# H1BR6.net
KiCad netlist of a schematic drawn in EAGLE
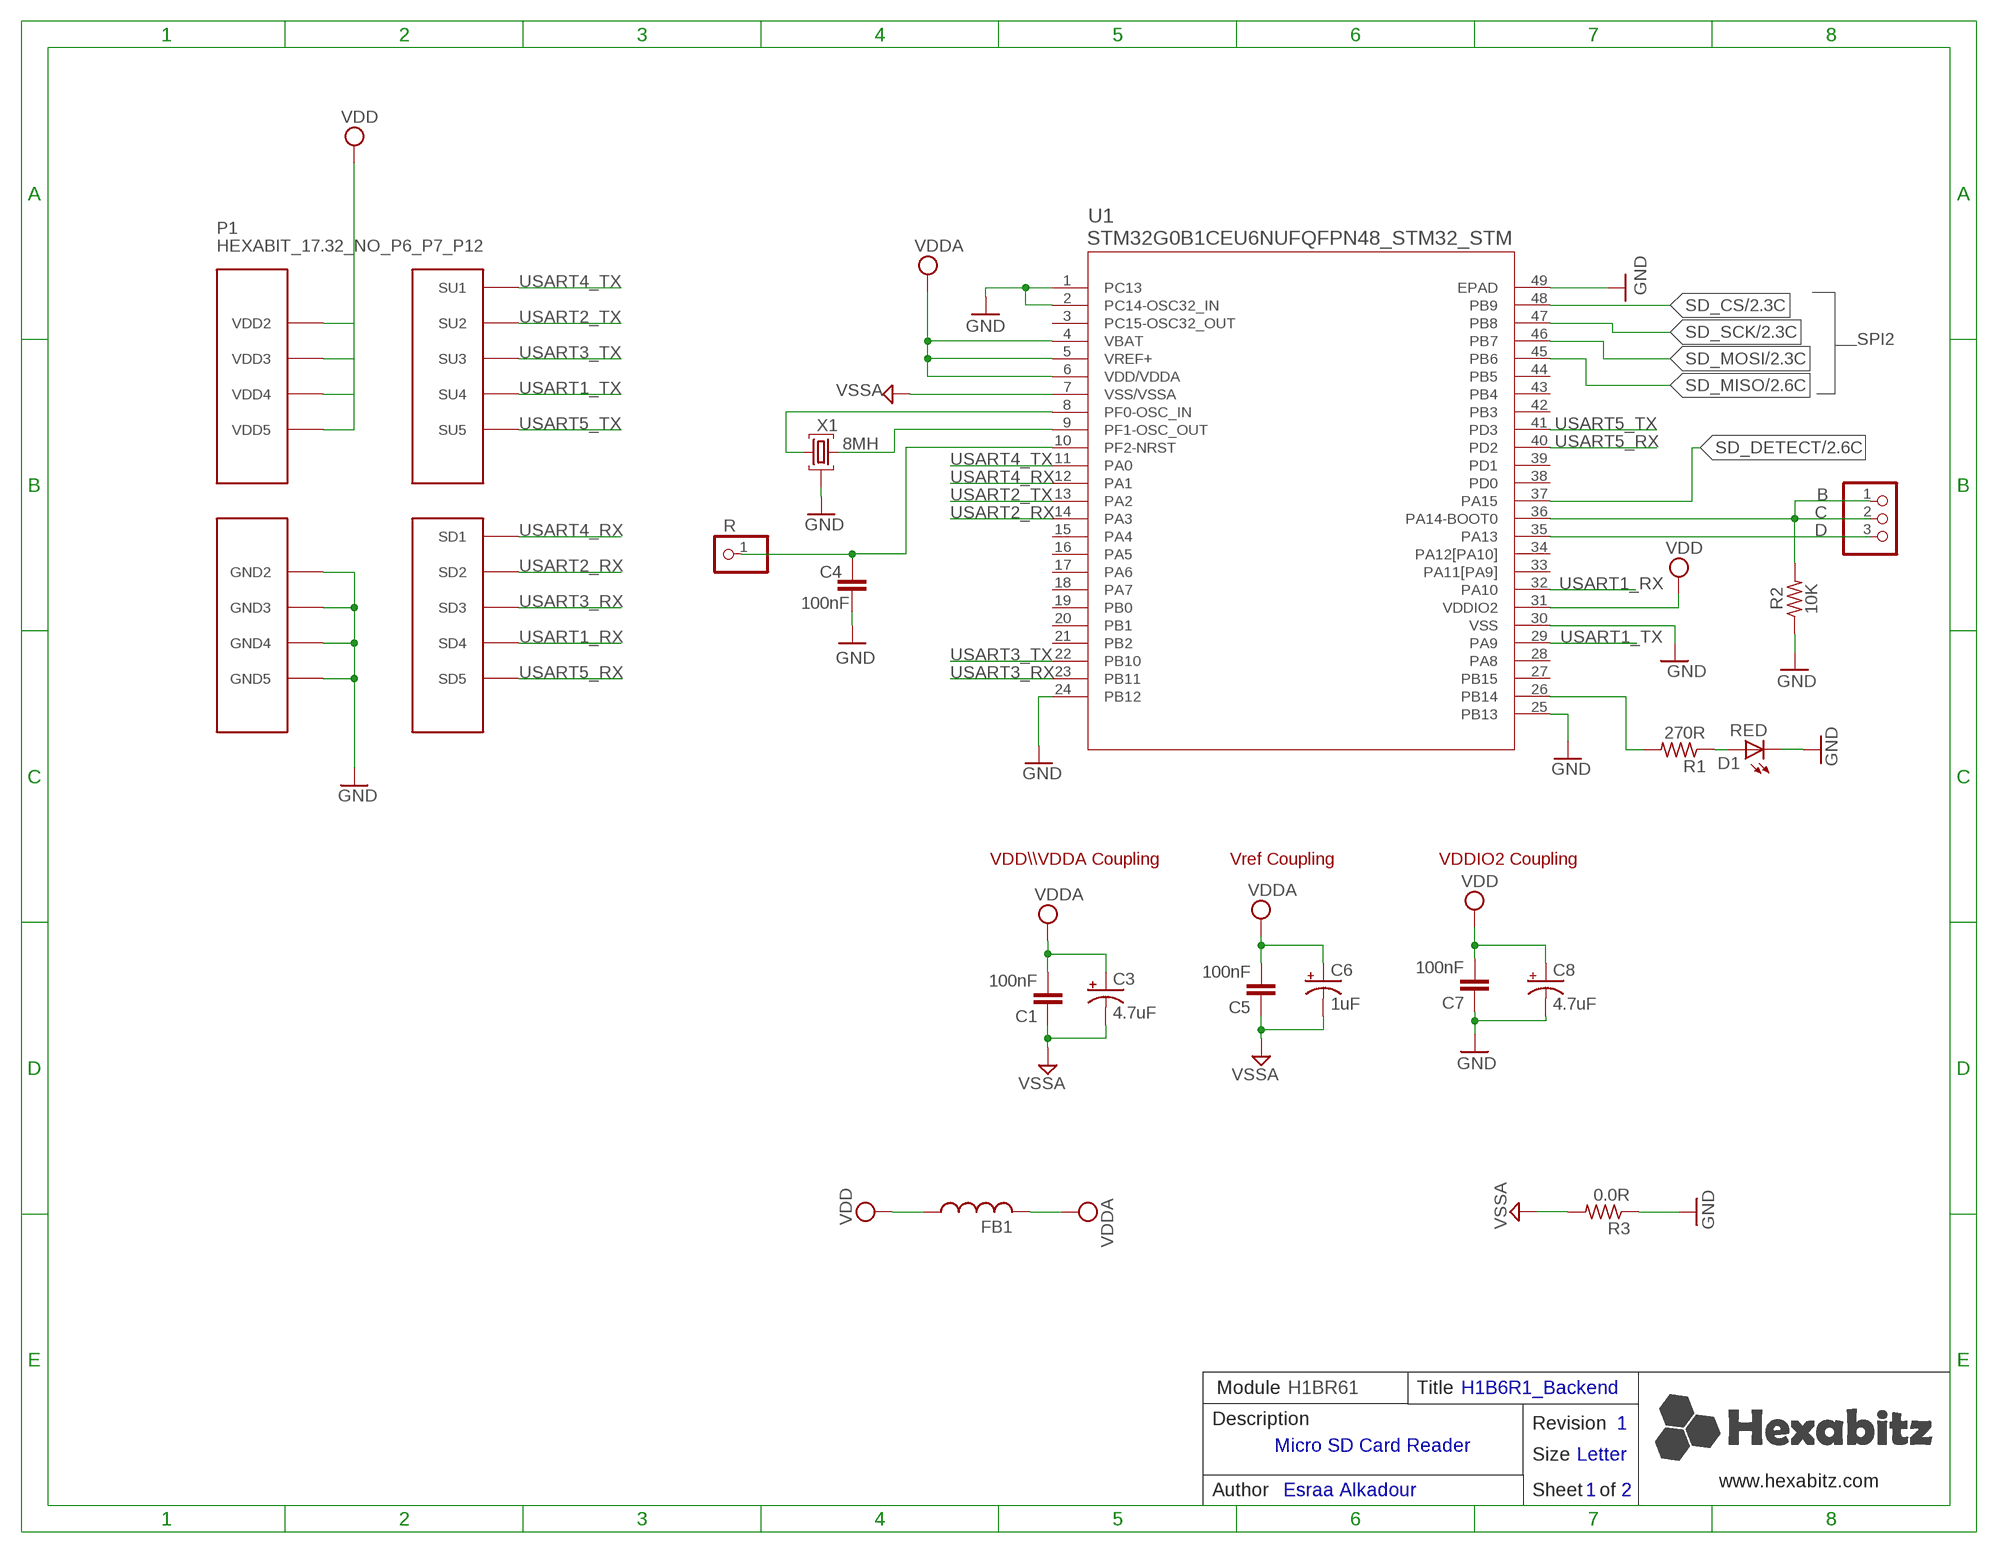
[diagram p0: schematic, sheet 1]
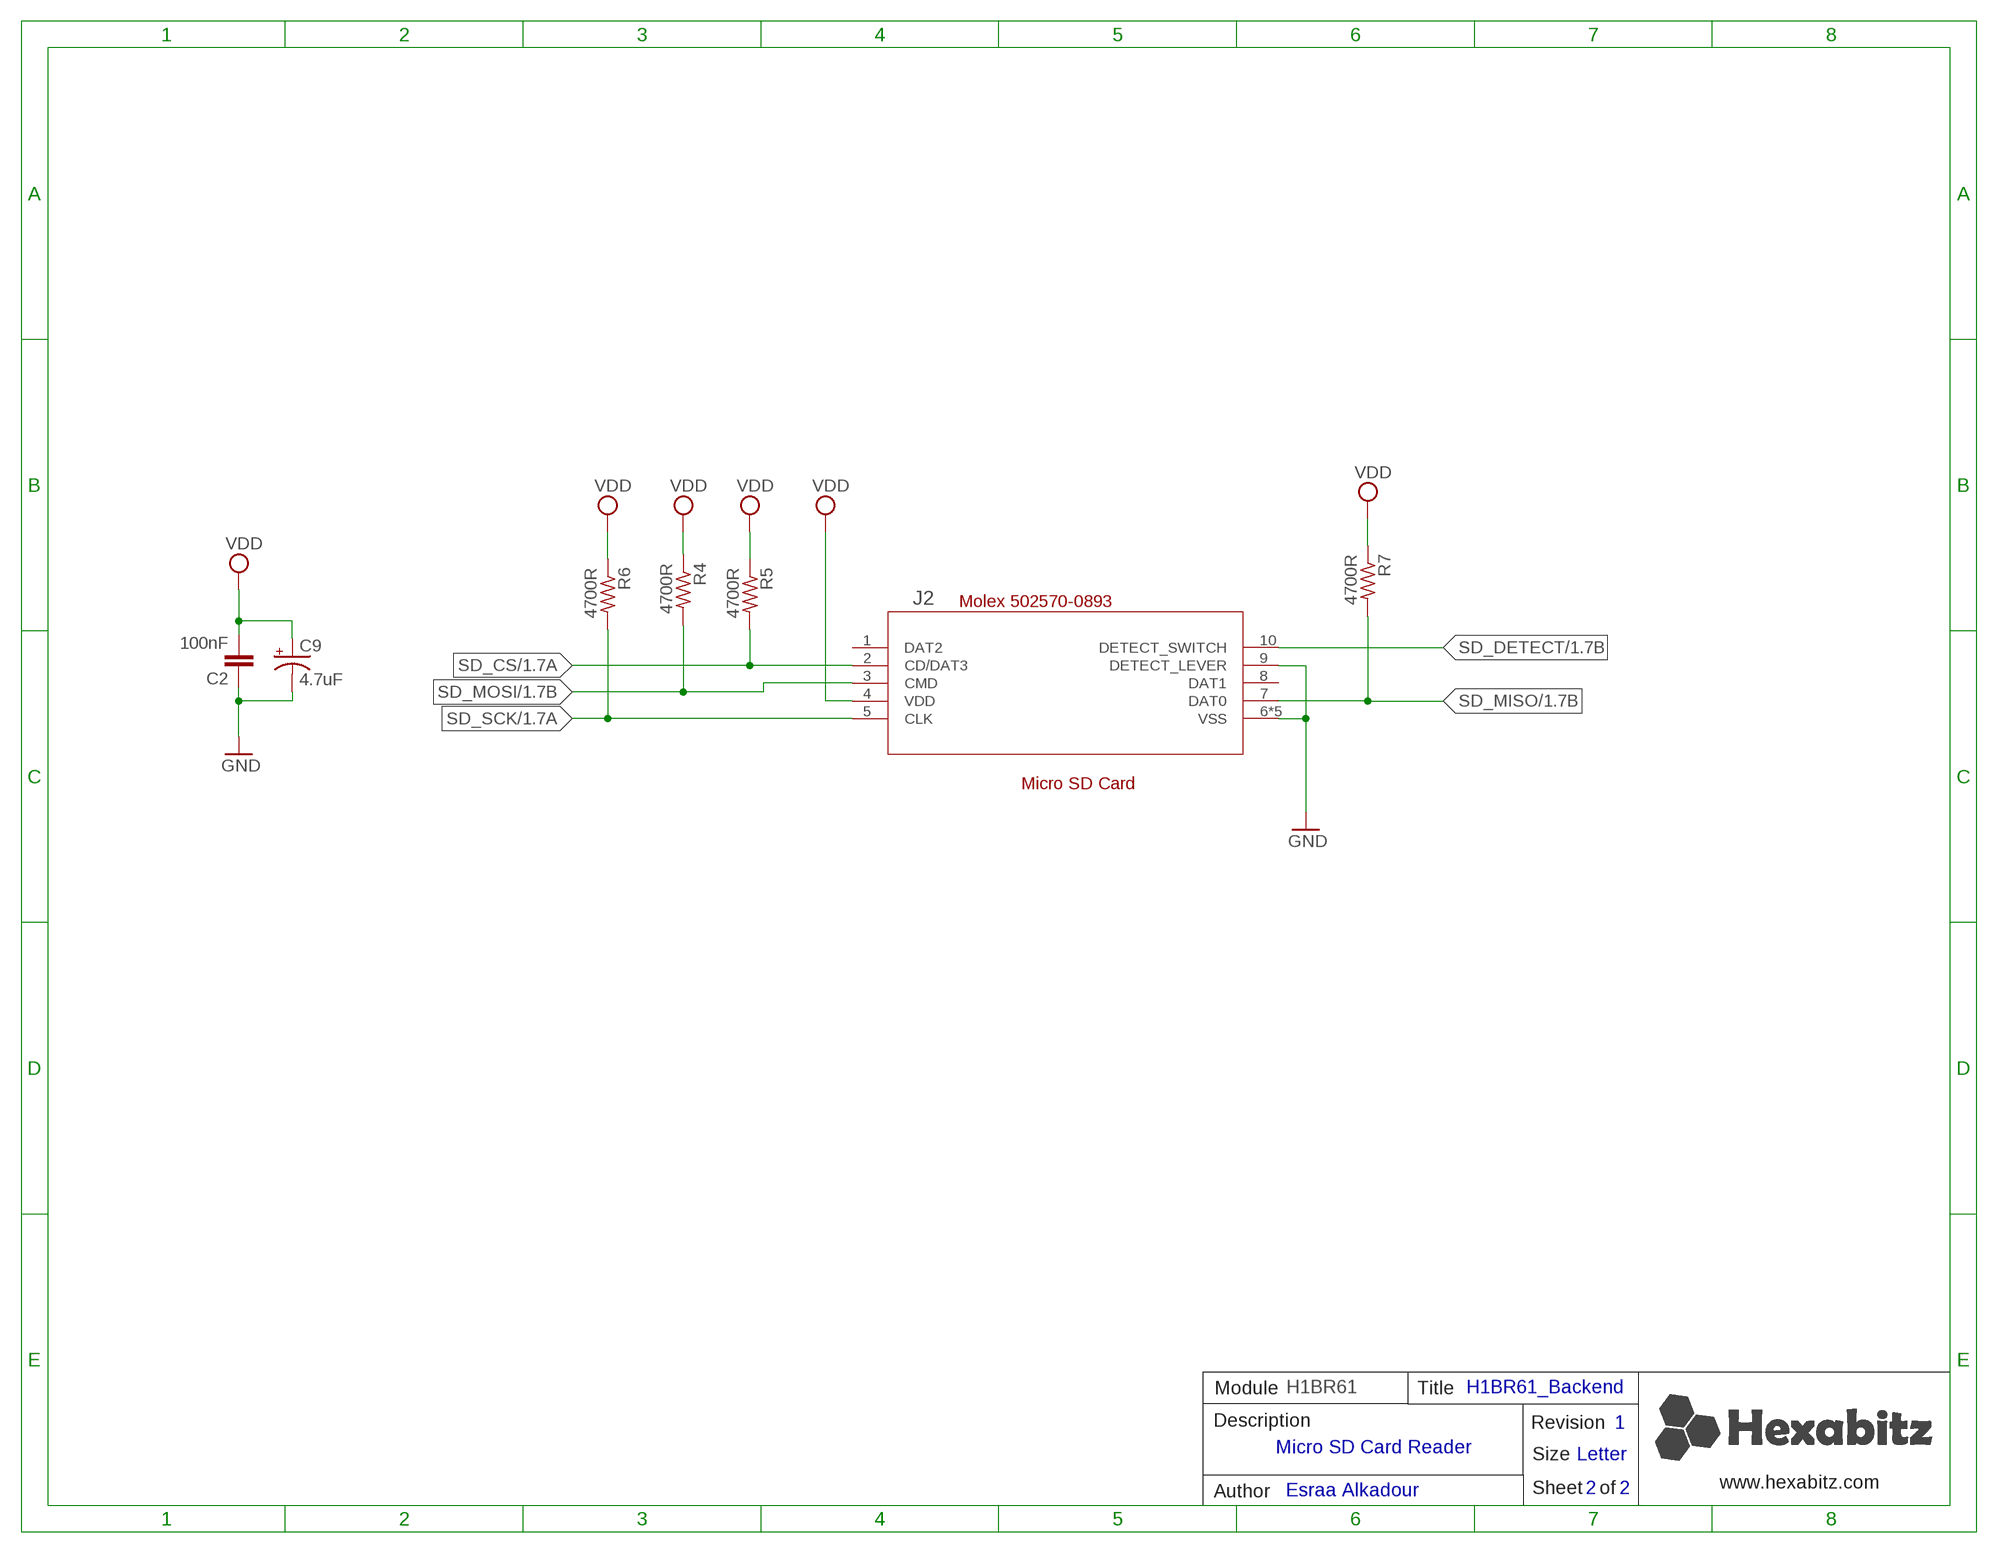
[diagram p1: schematic, sheet 2]

(export (version "E")
  (design (tool "Eeschema 10.0.6"))
  (components
    (comp (ref "C2")
      (value "100nF")
      (footprint "eagle-import:C-0603")
      (fields
        (field (name "CAPACITANCE") "100nF")
        (field (name "MFN") "AVX CORPORATION")
        (field (name "MPN") "'0603YC104K4T2A")
        (field (name "OCTOPART_URL") "'https://octopart.com/0603yc104k4t2a-avx+interconnect+%2F+elco-8120651")
        (field (name "TOLERANCE") "10%")
        (field (name "VOLTAGE_RATING") "16.0 V")
      )
      (libsource (lib "eagle-import") (part "C-0603"))
    )
    (comp (ref "C9")
      (value "4.7uF")
      (footprint "eagle-import:C-0805-POL")
      (fields
        (field (name "CAPACITANCE") "4.7uF")
        (field (name "MFN") "'Panasonic")
        (field (name "MPN") "'10TPU4R7MSI")
        (field (name "OCTOPART_URL") "https://octopart.com/10tpu4r7msi-panasonic-29487748?r=sp")
        (field (name "TOLERANCE") "20%")
        (field (name "VOLTAGE_RATING") "10.0 V")
      )
      (libsource (lib "eagle-import") (part "C-0805-POL"))
    )
    (comp (ref "J2")
      (value "5025700893502570-0893_MOL")
      (footprint "eagle-import:502570-0893_MOL")
      (fields
        (field (name "MANUFACTURER_PART_NUMBER") "5025700893")
        (field (name "COPYRIGHT") "Copyright (C) 2022 Ultra Librarian. All rights reserved.")
      )
      (libsource (lib "eagle-import") (part "5025700893502570-0893_MOL"))
    )
    (comp (ref "R4")
      (value "4700R")
      (footprint "eagle-import:R-0603")
      (fields
        (field (name "MFN") "YAGED [VA]")
        (field (name "MPN") "RC0603JR-074K7L")
        (field (name "OCTOPART_URL") "'https://octopart.com/rc0603jr-074k7l-yageo-55458509?r=sp")
        (field (name "RESISTANCE") "4700 Ohm")
        (field (name "TOLERANCE") "5%")
      )
      (libsource (lib "eagle-import") (part "R-0603"))
    )
    (comp (ref "R5")
      (value "4700R")
      (footprint "eagle-import:R-0603")
      (fields
        (field (name "MFN") "YAGED [VA]")
        (field (name "MPN") "RC0603JR-074K7L")
        (field (name "OCTOPART_URL") "'https://octopart.com/rc0603jr-074k7l-yageo-55458509?r=sp")
        (field (name "RESISTANCE") "4700 Ohm")
        (field (name "TOLERANCE") "5%")
      )
      (libsource (lib "eagle-import") (part "R-0603"))
    )
    (comp (ref "R6")
      (value "4700R")
      (footprint "eagle-import:R-0603")
      (fields
        (field (name "MFN") "YAGED [VA]")
        (field (name "MPN") "RC0603JR-074K7L")
        (field (name "OCTOPART_URL") "'https://octopart.com/rc0603jr-074k7l-yageo-55458509?r=sp")
        (field (name "RESISTANCE") "4700 Ohm")
        (field (name "TOLERANCE") "5%")
      )
      (libsource (lib "eagle-import") (part "R-0603"))
    )
    (comp (ref "R7")
      (value "4700R")
      (footprint "eagle-import:R-0603")
      (fields
        (field (name "MFN") "YAGED [VA]")
        (field (name "MPN") "RC0603JR-074K7L")
        (field (name "OCTOPART_URL") "'https://octopart.com/rc0603jr-074k7l-yageo-55458509?r=sp")
        (field (name "RESISTANCE") "4700 Ohm")
        (field (name "TOLERANCE") "5%")
      )
      (libsource (lib "eagle-import") (part "R-0603"))
    )
    (comp (ref "C1")
      (value "100nF")
      (footprint "eagle-import:C-0603")
      (fields
        (field (name "CAPACITANCE") "100nF")
        (field (name "MFN") "AVX CORPORATION")
        (field (name "MPN") "'0603YC104K4T2A")
        (field (name "OCTOPART_URL") "'https://octopart.com/0603yc104k4t2a-avx+interconnect+%2F+elco-8120651")
        (field (name "TOLERANCE") "10%")
        (field (name "VOLTAGE_RATING") "16.0 V")
      )
      (libsource (lib "eagle-import") (part "C-0603"))
    )
    (comp (ref "C3")
      (value "4.7uF")
      (footprint "eagle-import:C-0805-POL")
      (fields
        (field (name "CAPACITANCE") "4.7uF")
        (field (name "MFN") "'Panasonic")
        (field (name "MPN") "'10TPU4R7MSI")
        (field (name "OCTOPART_URL") "https://octopart.com/10tpu4r7msi-panasonic-29487748?r=sp")
        (field (name "TOLERANCE") "20%")
        (field (name "VOLTAGE_RATING") "10.0 V")
      )
      (libsource (lib "eagle-import") (part "C-0805-POL"))
    )
    (comp (ref "C4")
      (value "100nF")
      (footprint "eagle-import:C-0603")
      (fields
        (field (name "CAPACITANCE") "100nF")
        (field (name "MFN") "AVX CORPORATION")
        (field (name "MPN") "0603YC104K4T2A")
        (field (name "OCTOPART_URL") "'https://octopart.com/0603yc104k4t2a-avx+interconnect+%2F+elco-8120651")
        (field (name "TOLERANCE") "10%")
        (field (name "VOLTAGE_RATING") "16.0 V")
      )
      (libsource (lib "eagle-import") (part "C-0603"))
    )
    (comp (ref "C5")
      (value "100nF")
      (footprint "eagle-import:C-0603")
      (fields
        (field (name "CAPACITANCE") "100nF")
        (field (name "MFN") "AVX CORPORATION")
        (field (name "MPN") "'0603YC104K4T2A")
        (field (name "OCTOPART_URL") "'https://octopart.com/0603yc104k4t2a-avx+interconnect+%2F+elco-8120651")
        (field (name "TOLERANCE") "10%")
        (field (name "VOLTAGE_RATING") "16.0 V")
      )
      (libsource (lib "eagle-import") (part "C-0603"))
    )
    (comp (ref "C6")
      (value "1uF")
      (footprint "eagle-import:C-0805-POL")
      (fields
        (field (name "CAPACITANCE") "4.7uF")
        (field (name "MFN") "'YAGEO [VA]")
        (field (name "MPN") "'CC0805KKX7R7BB105")
        (field (name "OCTOPART_URL") "'https://octopart.com/cc0805kkx7r7bb105-yageo-8376555?r=sp")
        (field (name "TOLERANCE") "20%")
        (field (name "VOLTAGE_RATING") "10.0 V")
      )
      (libsource (lib "eagle-import") (part "C-0805-POL"))
    )
    (comp (ref "C7")
      (value "100nF")
      (footprint "eagle-import:C-0603")
      (fields
        (field (name "CAPACITANCE") "100nF")
        (field (name "MFN") "AVX CORPORATION")
        (field (name "MPN") "'0603YC104K4T2A")
        (field (name "OCTOPART_URL") "'https://octopart.com/0603yc104k4t2a-avx+interconnect+%2F+elco-8120651")
        (field (name "TOLERANCE") "10%")
        (field (name "VOLTAGE_RATING") "16.0 V")
      )
      (libsource (lib "eagle-import") (part "C-0603"))
    )
    (comp (ref "C8")
      (value "4.7uF")
      (footprint "eagle-import:C-0805-POL")
      (fields
        (field (name "CAPACITANCE") "1.00uF")
        (field (name "MFN") "'Panasonic")
        (field (name "MPN") "'10TPU4R7MSI")
        (field (name "OCTOPART_URL") "https://octopart.com/10tpu4r7msi-panasonic-29487748?r=sp")
        (field (name "TOLERANCE") "10%")
        (field (name "VOLTAGE_RATING") "16.0 V")
      )
      (libsource (lib "eagle-import") (part "C-0805-POL"))
    )
    (comp (ref "D1")
      (value "RED")
      (footprint "eagle-import:VLMS1300-GS08")
      (fields (field (name "MPN") "VLMS1300-GS08"))
      (libsource (lib "eagle-import") (part "VLMS1300-GS08"))
    )
    (comp (ref "FB1")
      (value "FB-TDK_MMZ1608Y300B")
      (footprint "eagle-import:FB-TDK_MMZ1608Y300B")
      (fields
        (field (name "MFN") "TDK ")
        (field (name "MPN") "MMZ1608Y300BTA00")
        (field (name "OCTOPART_URL") "https://octopart.com/mmz1608y300bta00-tdk-7906990?r=sp")
      )
      (libsource (lib "eagle-import") (part "FB-TDK_MMZ1608Y300B"))
    )
    (comp (ref "J4")
      (value "PINHD-1X1")
      (footprint "eagle-import:1X01")
      (fields (field (name "MPN") "87227-1"))
      (libsource (lib "eagle-import") (part "PINHD-1X1"))
    )
    (comp (ref "JP1")
      (value "PINHD-1X3")
      (footprint "eagle-import:1X03")
      (libsource (lib "eagle-import") (part "PINHD-1X3"))
    )
    (comp (ref "P1")
      (value "HEXABIT_17.32_NO_P6_P7_P12")
      (footprint "eagle-import:HEXABIT_17.32_NO_P6_P7_P12")
      (libsource (lib "eagle-import") (part "HEXABIT_?_NO_P6_P7_P1217.32"))
    )
    (comp (ref "R1")
      (value "270R")
      (footprint "eagle-import:R-0603")
      (fields
        (field (name "MFN") "'Panasonic")
        (field (name "MPN") "'ERJ-3GEYJ271V")
        (field (name "OCTOPART_URL") "https://octopart.com/erj-3geyj271v-panasonic-55560546?r=sp")
        (field (name "RESISTANCE") "270R")
      )
      (libsource (lib "eagle-import") (part "R-0603"))
    )
    (comp (ref "R2")
      (value "10K")
      (footprint "eagle-import:R-0603")
      (fields
        (field (name "MFN") "Vishay")
        (field (name "MPN") "'060300J0103T5E")
        (field (name "OCTOPART_URL") "https://octopart.com/search?q=060300J0103T5E&currency=USD&specs=0")
        (field (name "RESISTANCE") "10K")
      )
      (libsource (lib "eagle-import") (part "R-0603"))
    )
    (comp (ref "R3")
      (value "0.0R")
      (footprint "eagle-import:R-0603")
      (fields
        (field (name "MFN") "YAGEO [VR]")
        (field (name "MPN") "RC0603JR-070RL")
        (field (name "OCTOPART_URL") "https://octopart.com/rc0603jr-070rl-yageo-1241539?r=sp")
        (field (name "RESISTANCE") "0R")
      )
      (libsource (lib "eagle-import") (part "R-0603"))
    )
    (comp (ref "U1")
      (value "STM32G0B1CEU6NUFQFPN48_STM32_STM")
      (footprint "eagle-import:UFQFPN48_STM32_STM")
      (fields
        (field (name "MPN") "STM32G0B1CEU6N")
        (field (name "OCTOPART_URL") "https://octopart.com/stm32g0b1ceu6n-stmicroelectronics-116364672?r=sp")
        (field (name "COPYRIGHT") "Copyright (C) 2022 Ultra Librarian. All rights reserved.")
      )
      (libsource (lib "eagle-import") (part "STM32G0B1CEU6NUFQFPN48_STM32_STM"))
    )
    (comp (ref "X1")
      (value "8MH")
      (footprint "eagle-import:XTALL_CSTCE8M00G52")
      (fields
        (field (name "MPN") "CSTCE8M00G52Z-R0")
        (field (name "MPN_1") "CSTNE8M00G550000R0")
        (field (name "OCTOPART_URL") "https://octopart.com/cstne8m00g550000r0-murata-91406934?r=sp")
      )
      (libsource (lib "eagle-import") (part "XTALL_CSTCE8M00G52"))
    )
  )
  (nets
    (net (code "1") (name "C") (class "Default")
      (node (ref "JP1") (pin "1") (pinfunction "1_1") (pintype "passive"))
      (node (ref "JP1") (pin "2") (pinfunction "2_2") (pintype "passive"))
      (node (ref "R2") (pin "2") (pinfunction "2_2") (pintype "passive"))
      (node (ref "U1") (pin "36") (pinfunction "PA14-BOOT0_36") (pintype "bidirectional"))
    )
    (net (code "2") (name "D") (class "Default")
      (node (ref "JP1") (pin "3") (pinfunction "3_3") (pintype "passive"))
      (node (ref "U1") (pin "35") (pinfunction "PA13_35") (pintype "bidirectional"))
    )
    (net (code "3") (name "GND") (class "Default")
      (node (ref "C2") (pin "1") (pinfunction "1_1") (pintype "passive"))
      (node (ref "C4") (pin "1") (pinfunction "1_1") (pintype "passive"))
      (node (ref "C7") (pin "1") (pinfunction "1_1") (pintype "passive"))
      (node (ref "C8") (pin "2") (pinfunction "-_2") (pintype "passive"))
      (node (ref "C9") (pin "2") (pinfunction "-_2") (pintype "passive"))
      (node (ref "D1") (pin "C") (pinfunction "C_C") (pintype "passive"))
      (node (ref "J2") (pin "11") (pinfunction "VSS_11") (pintype "passive"))
      (node (ref "J2") (pin "12") (pinfunction "VSS_12") (pintype "passive"))
      (node (ref "J2") (pin "13") (pinfunction "VSS_13") (pintype "passive"))
      (node (ref "J2") (pin "14") (pinfunction "VSS_14") (pintype "passive"))
      (node (ref "J2") (pin "6") (pinfunction "VSS_6") (pintype "passive"))
      (node (ref "J2") (pin "9") (pinfunction "DETECT_LEVER_9") (pintype "passive"))
      (node (ref "P1") (pin "PAD_PD10") (pinfunction "GND4_PAD_PD10") (pintype "power_in"))
      (node (ref "P1") (pin "PAD_PD11") (pinfunction "GND5_PAD_PD11") (pintype "power_in"))
      (node (ref "P1") (pin "PAD_PD8") (pinfunction "GND2_PAD_PD8") (pintype "power_in"))
      (node (ref "P1") (pin "PAD_PD9") (pinfunction "GND3_PAD_PD9") (pintype "power_in"))
      (node (ref "R2") (pin "1") (pinfunction "1_1") (pintype "passive"))
      (node (ref "R3") (pin "1") (pinfunction "1_1") (pintype "passive"))
      (node (ref "U1") (pin "1") (pinfunction "PC13_1") (pintype "bidirectional"))
      (node (ref "U1") (pin "2") (pinfunction "PC14-OSC32_IN_2") (pintype "bidirectional"))
      (node (ref "U1") (pin "24") (pinfunction "PB12_24") (pintype "bidirectional"))
      (node (ref "U1") (pin "25") (pinfunction "PB13_25") (pintype "bidirectional"))
      (node (ref "U1") (pin "30") (pinfunction "VSS_30") (pintype "passive"))
      (node (ref "U1") (pin "49") (pinfunction "EPAD_49") (pintype "passive"))
      (node (ref "X1") (pin "P$2") (pinfunction "2_P$2") (pintype "passive"))
    )
    (net (code "4") (name "GND1") (class "Default")
      (node (ref "C1") (pin "1") (pinfunction "1_1") (pintype "passive"))
      (node (ref "C3") (pin "2") (pinfunction "-_2") (pintype "passive"))
      (node (ref "C5") (pin "1") (pinfunction "1_1") (pintype "passive"))
      (node (ref "C6") (pin "2") (pinfunction "-_2") (pintype "passive"))
      (node (ref "R3") (pin "2") (pinfunction "2_2") (pintype "passive"))
      (node (ref "U1") (pin "7") (pinfunction "VSS/VSSA_7") (pintype "passive"))
    )
    (net (code "5") (name "Net-(D1-PadA)") (class "Default")
      (node (ref "D1") (pin "A") (pinfunction "A_A") (pintype "passive"))
      (node (ref "R1") (pin "1") (pinfunction "1_1") (pintype "passive"))
    )
    (net (code "6") (name "Net-(U1-PB14)") (class "Default")
      (node (ref "R1") (pin "2") (pinfunction "2_2") (pintype "passive"))
      (node (ref "U1") (pin "26") (pinfunction "PB14_26") (pintype "bidirectional"))
    )
    (net (code "7") (name "Net-(U1-PF0-OSC_IN)") (class "Default")
      (node (ref "U1") (pin "8") (pinfunction "PF0-OSC_IN_8") (pintype "bidirectional"))
      (node (ref "X1") (pin "P$3") (pinfunction "3_P$3") (pintype "passive"))
    )
    (net (code "8") (name "Net-(U1-PF1-OSC_OUT)") (class "Default")
      (node (ref "U1") (pin "9") (pinfunction "PF1-OSC_OUT_9") (pintype "bidirectional"))
      (node (ref "X1") (pin "P$1") (pinfunction "1_P$1") (pintype "passive"))
    )
    (net (code "9") (name "Net-(U1-PF2-NRST)") (class "Default")
      (node (ref "C4") (pin "2") (pinfunction "2_2") (pintype "passive"))
      (node (ref "J4") (pin "1") (pinfunction "1_1") (pintype "passive"))
      (node (ref "U1") (pin "10") (pinfunction "PF2-NRST_10") (pintype "bidirectional"))
    )
    (net (code "10") (name "SD_CS") (class "Default")
      (node (ref "J2") (pin "2") (pinfunction "CD/DAT3_2") (pintype "passive"))
      (node (ref "R5") (pin "2") (pinfunction "2_2") (pintype "passive"))
      (node (ref "U1") (pin "48") (pinfunction "PB9_48") (pintype "bidirectional"))
    )
    (net (code "11") (name "SD_DETECT") (class "Default")
      (node (ref "J2") (pin "10") (pinfunction "DETECT_SWITCH_10") (pintype "passive"))
      (node (ref "U1") (pin "37") (pinfunction "PA15_37") (pintype "bidirectional"))
    )
    (net (code "12") (name "SD_MISO") (class "Default")
      (node (ref "J2") (pin "7") (pinfunction "DAT0_7") (pintype "bidirectional"))
      (node (ref "R7") (pin "2") (pinfunction "2_2") (pintype "passive"))
      (node (ref "U1") (pin "45") (pinfunction "PB6_45") (pintype "bidirectional"))
    )
    (net (code "13") (name "SD_MOSI") (class "Default")
      (node (ref "J2") (pin "3") (pinfunction "CMD_3") (pintype "passive"))
      (node (ref "R4") (pin "2") (pinfunction "2_2") (pintype "passive"))
      (node (ref "U1") (pin "46") (pinfunction "PB7_46") (pintype "bidirectional"))
    )
    (net (code "14") (name "SD_SCK") (class "Default")
      (node (ref "J2") (pin "5") (pinfunction "CLK_5") (pintype "passive"))
      (node (ref "R6") (pin "2") (pinfunction "2_2") (pintype "passive"))
      (node (ref "U1") (pin "47") (pinfunction "PB8_47") (pintype "bidirectional"))
    )
    (net (code "15") (name "USART1_RX") (class "Default")
      (node (ref "P1") (pin "PAD_PD4") (pinfunction "SD4_PAD_PD4") (pintype "bidirectional"))
      (node (ref "U1") (pin "32") (pinfunction "PA10_32") (pintype "bidirectional"))
    )
    (net (code "16") (name "USART1_TX") (class "Default")
      (node (ref "P1") (pin "PAD_PU4") (pinfunction "SU4_PAD_PU4") (pintype "bidirectional"))
      (node (ref "U1") (pin "29") (pinfunction "PA9_29") (pintype "bidirectional"))
    )
    (net (code "17") (name "USART2_RX") (class "Default")
      (node (ref "P1") (pin "PAD_PD2") (pinfunction "SD2_PAD_PD2") (pintype "bidirectional"))
      (node (ref "U1") (pin "14") (pinfunction "PA3_14") (pintype "bidirectional"))
    )
    (net (code "18") (name "USART2_TX") (class "Default")
      (node (ref "P1") (pin "PAD_PU2") (pinfunction "SU2_PAD_PU2") (pintype "bidirectional"))
      (node (ref "U1") (pin "13") (pinfunction "PA2_13") (pintype "bidirectional"))
    )
    (net (code "19") (name "USART3_RX") (class "Default")
      (node (ref "P1") (pin "PAD_PD3") (pinfunction "SD3_PAD_PD3") (pintype "bidirectional"))
      (node (ref "U1") (pin "23") (pinfunction "PB11_23") (pintype "bidirectional"))
    )
    (net (code "20") (name "USART3_TX") (class "Default")
      (node (ref "P1") (pin "PAD_PU3") (pinfunction "SU3_PAD_PU3") (pintype "bidirectional"))
      (node (ref "U1") (pin "22") (pinfunction "PB10_22") (pintype "bidirectional"))
    )
    (net (code "21") (name "USART4_RX") (class "Default")
      (node (ref "P1") (pin "PAD_PD1") (pinfunction "SD1_PAD_PD1") (pintype "bidirectional"))
      (node (ref "U1") (pin "12") (pinfunction "PA1_12") (pintype "bidirectional"))
    )
    (net (code "22") (name "USART4_TX") (class "Default")
      (node (ref "P1") (pin "PAD_PU1") (pinfunction "SU1_PAD_PU1") (pintype "bidirectional"))
      (node (ref "U1") (pin "11") (pinfunction "PA0_11") (pintype "bidirectional"))
    )
    (net (code "23") (name "USART5_RX") (class "Default")
      (node (ref "P1") (pin "PAD_PD5") (pinfunction "SD5_PAD_PD5") (pintype "bidirectional"))
      (node (ref "U1") (pin "40") (pinfunction "PD2_40") (pintype "bidirectional"))
    )
    (net (code "24") (name "USART5_TX") (class "Default")
      (node (ref "P1") (pin "PAD_PU5") (pinfunction "SU5_PAD_PU5") (pintype "bidirectional"))
      (node (ref "U1") (pin "41") (pinfunction "PD3_41") (pintype "bidirectional"))
    )
    (net (code "25") (name "VCC") (class "Default")
      (node (ref "C1") (pin "2") (pinfunction "2_2") (pintype "passive"))
      (node (ref "C3") (pin "1") (pinfunction "+_1") (pintype "passive"))
      (node (ref "C5") (pin "2") (pinfunction "2_2") (pintype "passive"))
      (node (ref "C6") (pin "1") (pinfunction "+_1") (pintype "passive"))
      (node (ref "FB1") (pin "2") (pinfunction "2_2") (pintype "passive"))
      (node (ref "U1") (pin "4") (pinfunction "VBAT_4") (pintype "power_in"))
      (node (ref "U1") (pin "5") (pinfunction "VREF+_5") (pintype "power_in"))
      (node (ref "U1") (pin "6") (pinfunction "VDD/VDDA_6") (pintype "power_in"))
    )
    (net (code "26") (name "VDD") (class "Default")
      (node (ref "C2") (pin "2") (pinfunction "2_2") (pintype "passive"))
      (node (ref "C7") (pin "2") (pinfunction "2_2") (pintype "passive"))
      (node (ref "C8") (pin "1") (pinfunction "+_1") (pintype "passive"))
      (node (ref "C9") (pin "1") (pinfunction "+_1") (pintype "passive"))
      (node (ref "FB1") (pin "1") (pinfunction "1_1") (pintype "passive"))
      (node (ref "J2") (pin "4") (pinfunction "VDD_4") (pintype "power_in"))
      (node (ref "P1") (pin "PAD_PU10") (pinfunction "VDD4_PAD_PU10") (pintype "power_in"))
      (node (ref "P1") (pin "PAD_PU11") (pinfunction "VDD5_PAD_PU11") (pintype "power_in"))
      (node (ref "P1") (pin "PAD_PU8") (pinfunction "VDD2_PAD_PU8") (pintype "power_in"))
      (node (ref "P1") (pin "PAD_PU9") (pinfunction "VDD3_PAD_PU9") (pintype "power_in"))
      (node (ref "R4") (pin "1") (pinfunction "1_1") (pintype "passive"))
      (node (ref "R5") (pin "1") (pinfunction "1_1") (pintype "passive"))
      (node (ref "R6") (pin "1") (pinfunction "1_1") (pintype "passive"))
      (node (ref "R7") (pin "1") (pinfunction "1_1") (pintype "passive"))
      (node (ref "U1") (pin "31") (pinfunction "VDDIO2_31") (pintype "power_in"))
    )
    (net (code "27") (name "unconnected-(J2-DAT1-Pad8)") (class "Default")
      (node (ref "J2") (pin "8") (pinfunction "DAT1_8") (pintype "bidirectional"))
    )
    (net (code "28") (name "unconnected-(J2-DAT2-Pad1)") (class "Default")
      (node (ref "J2") (pin "1") (pinfunction "DAT2_1") (pintype "bidirectional"))
    )
    (net (code "29") (name "unconnected-(U1-PA4-Pad15)") (class "Default")
      (node (ref "U1") (pin "15") (pinfunction "PA4_15") (pintype "bidirectional"))
    )
    (net (code "30") (name "unconnected-(U1-PA5-Pad16)") (class "Default")
      (node (ref "U1") (pin "16") (pinfunction "PA5_16") (pintype "bidirectional"))
    )
    (net (code "31") (name "unconnected-(U1-PA6-Pad17)") (class "Default")
      (node (ref "U1") (pin "17") (pinfunction "PA6_17") (pintype "bidirectional"))
    )
    (net (code "32") (name "unconnected-(U1-PA7-Pad18)") (class "Default")
      (node (ref "U1") (pin "18") (pinfunction "PA7_18") (pintype "bidirectional"))
    )
    (net (code "33") (name "unconnected-(U1-PA8-Pad28)") (class "Default")
      (node (ref "U1") (pin "28") (pinfunction "PA8_28") (pintype "bidirectional"))
    )
    (net (code "34") (name "unconnected-(U1-PA11[PA9]-Pad33)") (class "Default")
      (node (ref "U1") (pin "33") (pinfunction "PA11[PA9]_33") (pintype "bidirectional"))
    )
    (net (code "35") (name "unconnected-(U1-PA12[PA10]-Pad34)") (class "Default")
      (node (ref "U1") (pin "34") (pinfunction "PA12[PA10]_34") (pintype "bidirectional"))
    )
    (net (code "36") (name "unconnected-(U1-PB0-Pad19)") (class "Default")
      (node (ref "U1") (pin "19") (pinfunction "PB0_19") (pintype "bidirectional"))
    )
    (net (code "37") (name "unconnected-(U1-PB1-Pad20)") (class "Default")
      (node (ref "U1") (pin "20") (pinfunction "PB1_20") (pintype "bidirectional"))
    )
    (net (code "38") (name "unconnected-(U1-PB2-Pad21)") (class "Default")
      (node (ref "U1") (pin "21") (pinfunction "PB2_21") (pintype "bidirectional"))
    )
    (net (code "39") (name "unconnected-(U1-PB3-Pad42)") (class "Default")
      (node (ref "U1") (pin "42") (pinfunction "PB3_42") (pintype "bidirectional"))
    )
    (net (code "40") (name "unconnected-(U1-PB4-Pad43)") (class "Default")
      (node (ref "U1") (pin "43") (pinfunction "PB4_43") (pintype "bidirectional"))
    )
    (net (code "41") (name "unconnected-(U1-PB5-Pad44)") (class "Default")
      (node (ref "U1") (pin "44") (pinfunction "PB5_44") (pintype "bidirectional"))
    )
    (net (code "42") (name "unconnected-(U1-PB15-Pad27)") (class "Default")
      (node (ref "U1") (pin "27") (pinfunction "PB15_27") (pintype "bidirectional"))
    )
    (net (code "43") (name "unconnected-(U1-PC15-OSC32_OUT-Pad3)") (class "Default")
      (node (ref "U1") (pin "3") (pinfunction "PC15-OSC32_OUT_3") (pintype "bidirectional"))
    )
    (net (code "44") (name "unconnected-(U1-PD0-Pad38)") (class "Default")
      (node (ref "U1") (pin "38") (pinfunction "PD0_38") (pintype "bidirectional"))
    )
    (net (code "45") (name "unconnected-(U1-PD1-Pad39)") (class "Default")
      (node (ref "U1") (pin "39") (pinfunction "PD1_39") (pintype "bidirectional"))
    )
  )
)
